# SchematicLAB-4.net
KiCad netlist of a schematic drawn in EAGLE
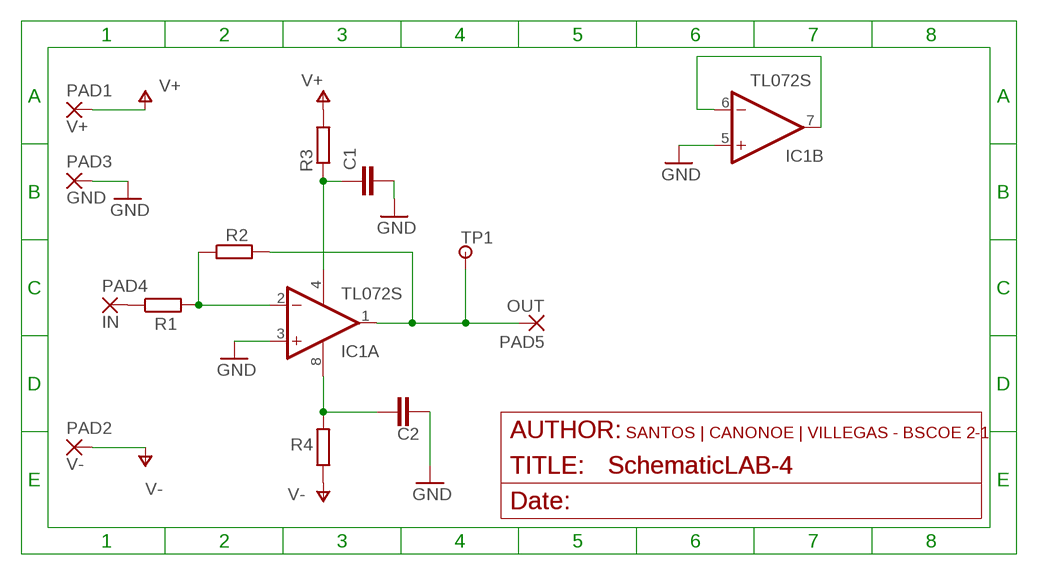
[diagram p0: schematic, sheet 1]

(export (version "E")
  (design (tool "Eeschema 10.0.6"))
  (components
    (comp (ref "C1")
      (value "C2.5P")
      (footprint "eagle-import:C025-030X050")
      (libsource (lib "eagle-import") (part "C2.5P"))
    )
    (comp (ref "C2")
      (value "C2.5P")
      (footprint "eagle-import:C025-030X050")
      (libsource (lib "eagle-import") (part "C2.5P"))
    )
    (comp (ref "IC1")
      (value "TL072S")
      (footprint "eagle-import:SOCKED-08")
      (libsource (lib "eagle-import") (part "TL072S"))
    )
    (comp (ref "PAD1")
      (value "V+")
      (footprint "eagle-import:2,54_1,1")
      (libsource (lib "eagle-import") (part "PAD-TERMINAL"))
    )
    (comp (ref "PAD2")
      (value "V-")
      (footprint "eagle-import:2,54_1,1")
      (libsource (lib "eagle-import") (part "PAD-TERMINAL"))
    )
    (comp (ref "PAD3")
      (value "GND")
      (footprint "eagle-import:2,54_1,1")
      (libsource (lib "eagle-import") (part "PAD-TERMINAL"))
    )
    (comp (ref "PAD4")
      (value "IN")
      (footprint "eagle-import:2,54_1,1")
      (libsource (lib "eagle-import") (part "PAD-TERMINAL"))
    )
    (comp (ref "PAD5")
      (value "OUT")
      (footprint "eagle-import:2,54_1,1")
      (libsource (lib "eagle-import") (part "PAD-TERMINAL"))
    )
    (comp (ref "R1")
      (value "R")
      (footprint "eagle-import:0207_10")
      (libsource (lib "eagle-import") (part "R"))
    )
    (comp (ref "R2")
      (value "R")
      (footprint "eagle-import:0207_10")
      (libsource (lib "eagle-import") (part "R"))
    )
    (comp (ref "R3")
      (value "R")
      (footprint "eagle-import:0207_10")
      (libsource (lib "eagle-import") (part "R"))
    )
    (comp (ref "R4")
      (value "R")
      (footprint "eagle-import:0207_10")
      (libsource (lib "eagle-import") (part "R"))
    )
    (comp (ref "TP1")
      (value "PAD-TESTPOINT")
      (footprint "eagle-import:1,6_0,8")
      (libsource (lib "eagle-import") (part "PAD-TESTPOINT"))
    )
  )
  (nets
    (net (code "1") (name "GND") (class "Default")
      (node (ref "C1") (pin "2") (pinfunction "2_2") (pintype "passive"))
      (node (ref "C2") (pin "1") (pinfunction "1_1") (pintype "passive"))
      (node (ref "IC1") (pin "3") (pinfunction "+IN_3") (pintype "input"))
      (node (ref "IC1") (pin "5") (pinfunction "+IN_5") (pintype "input"))
      (node (ref "PAD3") (pin "1") (pinfunction "P_1") (pintype "passive"))
    )
    (net (code "2") (name "Net-(IC1A--IN)") (class "Default")
      (node (ref "IC1") (pin "2") (pinfunction "-IN_2") (pintype "input"))
      (node (ref "R1") (pin "2") (pinfunction "2_2") (pintype "passive"))
      (node (ref "R2") (pin "1") (pinfunction "1_1") (pintype "passive"))
    )
    (net (code "3") (name "Net-(IC1A-OUT)") (class "Default")
      (node (ref "IC1") (pin "1") (pinfunction "OUT_1") (pintype "output"))
      (node (ref "PAD5") (pin "1") (pinfunction "P_1") (pintype "passive"))
      (node (ref "R2") (pin "2") (pinfunction "2_2") (pintype "passive"))
      (node (ref "TP1") (pin "1") (pinfunction "P_1") (pintype "passive"))
    )
    (net (code "4") (name "Net-(IC1A-V+)") (class "Default")
      (node (ref "C2") (pin "2") (pinfunction "2_2") (pintype "passive"))
      (node (ref "IC1") (pin "8") (pinfunction "V+_8") (pintype "power_in"))
      (node (ref "R4") (pin "2") (pinfunction "2_2") (pintype "passive"))
    )
    (net (code "5") (name "Net-(IC1A-V-)") (class "Default")
      (node (ref "C1") (pin "1") (pinfunction "1_1") (pintype "passive"))
      (node (ref "IC1") (pin "4") (pinfunction "V-_4") (pintype "power_in"))
      (node (ref "R3") (pin "1") (pinfunction "1_1") (pintype "passive"))
    )
    (net (code "6") (name "Net-(IC1B--IN)") (class "Default")
      (node (ref "IC1") (pin "6") (pinfunction "-IN_6") (pintype "input"))
      (node (ref "IC1") (pin "7") (pinfunction "OUT_7") (pintype "output"))
    )
    (net (code "7") (name "Net-(PAD4-P)") (class "Default")
      (node (ref "PAD4") (pin "1") (pinfunction "P_1") (pintype "passive"))
      (node (ref "R1") (pin "1") (pinfunction "1_1") (pintype "passive"))
    )
    (net (code "8") (name "V+") (class "Default")
      (node (ref "PAD1") (pin "1") (pinfunction "P_1") (pintype "passive"))
      (node (ref "R3") (pin "2") (pinfunction "2_2") (pintype "passive"))
    )
    (net (code "9") (name "V-") (class "Default")
      (node (ref "PAD2") (pin "1") (pinfunction "P_1") (pintype "passive"))
      (node (ref "R4") (pin "1") (pinfunction "1_1") (pintype "passive"))
    )
  )
)
